# 10-DashLEDs.net
KiCad netlist of a schematic drawn in Altium Designer
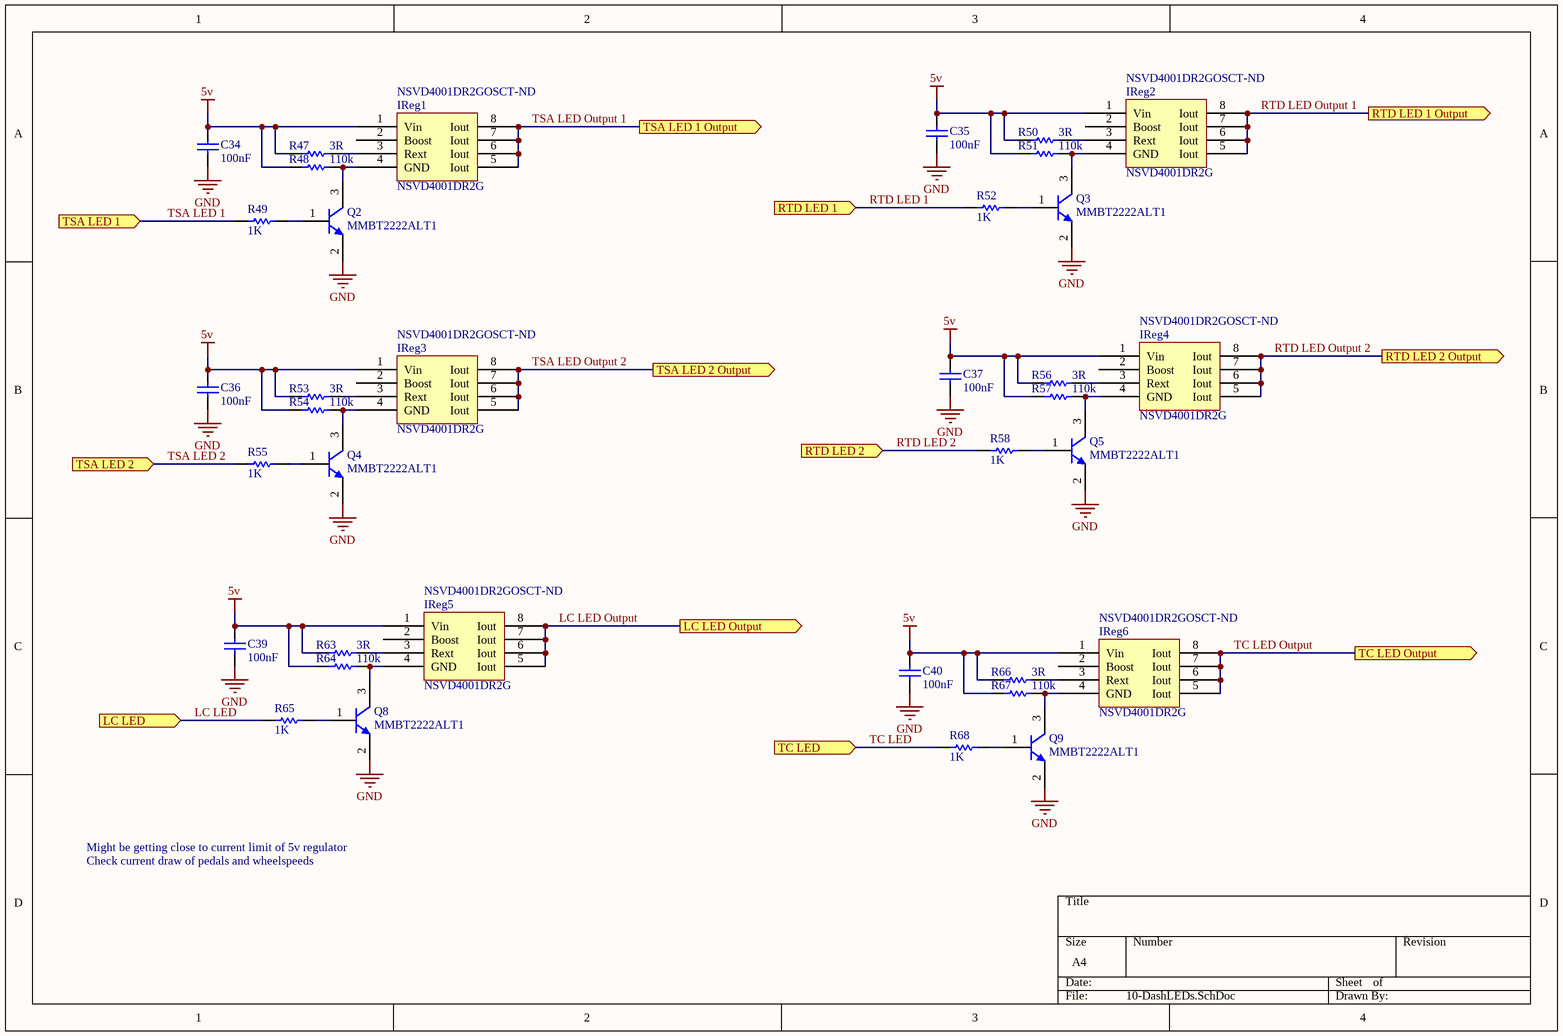
[diagram p0: 10-DashLEDs.SchDoc]

(export (version "E")
  (design (tool "Eeschema 10.0.6"))
  (components
    (comp (ref "C34")
      (value "100nF")
      (footprint "1608[0603]")
      (description "Capacitor")
      (fields
        (field (name "MANUFACTURER") "Yageo")
        (field (name "MANUFACTURER PART NUMBER") "CC0603KRX7R9BB104")
      )
      (libsource (lib "Miscellaneous Devices") (part "Cap"))
    )
    (comp (ref "C35")
      (value "100nF")
      (footprint "1608[0603]")
      (description "Capacitor")
      (fields
        (field (name "MANUFACTURER") "Yageo")
        (field (name "MANUFACTURER PART NUMBER") "CC0603KRX7R9BB104")
      )
      (libsource (lib "Miscellaneous Devices") (part "Cap"))
    )
    (comp (ref "C36")
      (value "100nF")
      (footprint "1608[0603]")
      (description "Capacitor")
      (fields
        (field (name "MANUFACTURER") "Yageo")
        (field (name "MANUFACTURER PART NUMBER") "CC0603KRX7R9BB104")
      )
      (libsource (lib "Miscellaneous Devices") (part "Cap"))
    )
    (comp (ref "C37")
      (value "100nF")
      (footprint "1608[0603]")
      (description "Capacitor")
      (fields
        (field (name "MANUFACTURER") "Yageo")
        (field (name "MANUFACTURER PART NUMBER") "CC0603KRX7R9BB104")
      )
      (libsource (lib "Miscellaneous Devices") (part "Cap"))
    )
    (comp (ref "C39")
      (value "100nF")
      (footprint "1608[0603]")
      (description "Capacitor")
      (fields
        (field (name "MANUFACTURER") "Yageo")
        (field (name "MANUFACTURER PART NUMBER") "CC0603KRX7R9BB104")
      )
      (libsource (lib "Miscellaneous Devices") (part "Cap"))
    )
    (comp (ref "C40")
      (value "100nF")
      (footprint "1608[0603]")
      (description "Capacitor")
      (fields
        (field (name "MANUFACTURER") "Yageo")
        (field (name "MANUFACTURER PART NUMBER") "CC0603KRX7R9BB104")
      )
      (libsource (lib "Miscellaneous Devices") (part "Cap"))
    )
    (comp (ref "IReg1")
      (value "NSVD4001DR2G")
      (footprint "SO8_M")
      (fields
        (field (name "MANUFACTURER") "ON Semiconductor")
        (field (name "MANUFACTURER PART NUMBER") "NUD4001DR2G")
        (field (name "SUPPLIER PART NUMBER 1") "NSVD4001DR2GOSCT-ND")
      )
      (libsource (lib "VCU Library") (part "LED Currnet Driver, 500mA, 30V max"))
    )
    (comp (ref "IReg2")
      (value "NSVD4001DR2G")
      (footprint "SO8_M")
      (fields
        (field (name "MANUFACTURER") "ON Semiconductor")
        (field (name "MANUFACTURER PART NUMBER") "NUD4001DR2G")
        (field (name "SUPPLIER PART NUMBER 1") "NSVD4001DR2GOSCT-ND")
      )
      (libsource (lib "VCU Library") (part "LED Currnet Driver, 500mA, 30V max"))
    )
    (comp (ref "IReg3")
      (value "NSVD4001DR2G")
      (footprint "SO8_M")
      (fields
        (field (name "MANUFACTURER") "ON Semiconductor")
        (field (name "MANUFACTURER PART NUMBER") "NUD4001DR2G")
        (field (name "SUPPLIER PART NUMBER 1") "NSVD4001DR2GOSCT-ND")
      )
      (libsource (lib "VCU Library") (part "LED Currnet Driver, 500mA, 30V max"))
    )
    (comp (ref "IReg4")
      (value "NSVD4001DR2G")
      (footprint "SO8_M")
      (fields
        (field (name "MANUFACTURER") "ON Semiconductor")
        (field (name "MANUFACTURER PART NUMBER") "NUD4001DR2G")
        (field (name "SUPPLIER PART NUMBER 1") "NSVD4001DR2GOSCT-ND")
      )
      (libsource (lib "VCU Library") (part "LED Currnet Driver, 500mA, 30V max"))
    )
    (comp (ref "IReg5")
      (value "NSVD4001DR2G")
      (footprint "SO8_M")
      (fields
        (field (name "MANUFACTURER") "ON Semiconductor")
        (field (name "MANUFACTURER PART NUMBER") "NUD4001DR2G")
        (field (name "SUPPLIER PART NUMBER 1") "NSVD4001DR2GOSCT-ND")
      )
      (libsource (lib "VCU Library") (part "LED Currnet Driver, 500mA, 30V max"))
    )
    (comp (ref "IReg6")
      (value "NSVD4001DR2G")
      (footprint "SO8_M")
      (fields
        (field (name "MANUFACTURER") "ON Semiconductor")
        (field (name "MANUFACTURER PART NUMBER") "NUD4001DR2G")
        (field (name "SUPPLIER PART NUMBER 1") "NSVD4001DR2GOSCT-ND")
      )
      (libsource (lib "VCU Library") (part "LED Currnet Driver, 500mA, 30V max"))
    )
    (comp (ref "Q2")
      (value "MMBT2222ALT1")
      (footprint "ONSC-SOT-23-3-318-08_V")
      (description "General Purpose Transistor, NPN Silicon, 3-Pin SOT-23, Tape and Reel")
      (fields (field (name "MANUFACTURER") "On Semiconductor"))
      (libsource (lib "Altium Content Vault") (part "ONSC-NPN-B1E2C3-3"))
    )
    (comp (ref "Q3")
      (value "MMBT2222ALT1")
      (footprint "ONSC-SOT-23-3-318-08_V")
      (description "General Purpose Transistor, NPN Silicon, 3-Pin SOT-23, Tape and Reel")
      (fields (field (name "MANUFACTURER") "On Semiconductor"))
      (libsource (lib "Altium Content Vault") (part "ONSC-NPN-B1E2C3-3"))
    )
    (comp (ref "Q4")
      (value "MMBT2222ALT1")
      (footprint "ONSC-SOT-23-3-318-08_V")
      (description "General Purpose Transistor, NPN Silicon, 3-Pin SOT-23, Tape and Reel")
      (fields (field (name "MANUFACTURER") "On Semiconductor"))
      (libsource (lib "Altium Content Vault") (part "ONSC-NPN-B1E2C3-3"))
    )
    (comp (ref "Q5")
      (value "MMBT2222ALT1")
      (footprint "ONSC-SOT-23-3-318-08_V")
      (description "General Purpose Transistor, NPN Silicon, 3-Pin SOT-23, Tape and Reel")
      (fields (field (name "MANUFACTURER") "On Semiconductor"))
      (libsource (lib "Altium Content Vault") (part "ONSC-NPN-B1E2C3-3"))
    )
    (comp (ref "Q8")
      (value "MMBT2222ALT1")
      (footprint "ONSC-SOT-23-3-318-08_V")
      (description "General Purpose Transistor, NPN Silicon, 3-Pin SOT-23, Tape and Reel")
      (fields (field (name "MANUFACTURER") "On Semiconductor"))
      (libsource (lib "Altium Content Vault") (part "ONSC-NPN-B1E2C3-3"))
    )
    (comp (ref "Q9")
      (value "MMBT2222ALT1")
      (footprint "ONSC-SOT-23-3-318-08_V")
      (description "General Purpose Transistor, NPN Silicon, 3-Pin SOT-23, Tape and Reel")
      (fields (field (name "MANUFACTURER") "On Semiconductor"))
      (libsource (lib "Altium Content Vault") (part "ONSC-NPN-B1E2C3-3"))
    )
    (comp (ref "R47")
      (value "3R")
      (footprint "1608[0603]")
      (description "Resistor")
      (fields
        (field (name "MANUFACTURER") "Yageo")
        (field (name "MANUFACTURER PART NUMBER") "RC0603FR-072RL")
      )
      (libsource (lib "Miscellaneous Devices") (part "Res1"))
    )
    (comp (ref "R48")
      (value "110k")
      (footprint "1608[0603]")
      (description "Resistor")
      (fields
        (field (name "MANUFACTURER") "Yageo")
        (field (name "MANUFACTURER PART NUMBER") "RC0603JR-07110KL")
      )
      (libsource (lib "Miscellaneous Devices") (part "Res1"))
    )
    (comp (ref "R49")
      (value "1K")
      (footprint "1608[0603]")
      (description "Resistor")
      (fields
        (field (name "MANUFACTURER") "Panasonic Electronic Components")
        (field (name "MANUFACTURER PART NUMBER") "ERJ-PA3F1001V")
      )
      (libsource (lib "Miscellaneous Devices") (part "Res1"))
    )
    (comp (ref "R50")
      (value "3R")
      (footprint "1608[0603]")
      (description "Resistor")
      (fields
        (field (name "MANUFACTURER") "Yageo")
        (field (name "MANUFACTURER PART NUMBER") "RC0603FR-072RL")
      )
      (libsource (lib "Miscellaneous Devices") (part "Res1"))
    )
    (comp (ref "R51")
      (value "110k")
      (footprint "1608[0603]")
      (description "Resistor")
      (fields
        (field (name "MANUFACTURER") "Yageo")
        (field (name "MANUFACTURER PART NUMBER") "RC0603JR-07110KL")
      )
      (libsource (lib "Miscellaneous Devices") (part "Res1"))
    )
    (comp (ref "R52")
      (value "1K")
      (footprint "1608[0603]")
      (description "Resistor")
      (fields
        (field (name "MANUFACTURER") "Panasonic Electronic Components")
        (field (name "MANUFACTURER PART NUMBER") "ERJ-PA3F1001V")
      )
      (libsource (lib "Miscellaneous Devices") (part "Res1"))
    )
    (comp (ref "R53")
      (value "3R")
      (footprint "1608[0603]")
      (description "Resistor")
      (fields
        (field (name "MANUFACTURER") "Yageo")
        (field (name "MANUFACTURER PART NUMBER") "RC0603FR-072RL")
      )
      (libsource (lib "Miscellaneous Devices") (part "Res1"))
    )
    (comp (ref "R54")
      (value "110k")
      (footprint "1608[0603]")
      (description "Resistor")
      (fields
        (field (name "MANUFACTURER") "Yageo")
        (field (name "MANUFACTURER PART NUMBER") "RC0603JR-07110KL")
      )
      (libsource (lib "Miscellaneous Devices") (part "Res1"))
    )
    (comp (ref "R55")
      (value "1K")
      (footprint "1608[0603]")
      (description "Resistor")
      (fields
        (field (name "MANUFACTURER") "Panasonic Electronic Components")
        (field (name "MANUFACTURER PART NUMBER") "ERJ-PA3F1001V")
      )
      (libsource (lib "Miscellaneous Devices") (part "Res1"))
    )
    (comp (ref "R56")
      (value "3R")
      (footprint "1608[0603]")
      (description "Resistor")
      (fields
        (field (name "MANUFACTURER") "Yageo")
        (field (name "MANUFACTURER PART NUMBER") "RC0603FR-072RL")
      )
      (libsource (lib "Miscellaneous Devices") (part "Res1"))
    )
    (comp (ref "R57")
      (value "110k")
      (footprint "1608[0603]")
      (description "Resistor")
      (fields
        (field (name "MANUFACTURER") "Yageo")
        (field (name "MANUFACTURER PART NUMBER") "RC0603JR-07110KL")
      )
      (libsource (lib "Miscellaneous Devices") (part "Res1"))
    )
    (comp (ref "R58")
      (value "1K")
      (footprint "1608[0603]")
      (description "Resistor")
      (fields
        (field (name "MANUFACTURER") "Panasonic Electronic Components")
        (field (name "MANUFACTURER PART NUMBER") "ERJ-PA3F1001V")
      )
      (libsource (lib "Miscellaneous Devices") (part "Res1"))
    )
    (comp (ref "R63")
      (value "3R")
      (footprint "1608[0603]")
      (description "Resistor")
      (fields
        (field (name "MANUFACTURER") "Yageo")
        (field (name "MANUFACTURER PART NUMBER") "RC0603FR-072RL")
      )
      (libsource (lib "Miscellaneous Devices") (part "Res1"))
    )
    (comp (ref "R64")
      (value "110k")
      (footprint "1608[0603]")
      (description "Resistor")
      (fields
        (field (name "MANUFACTURER") "Yageo")
        (field (name "MANUFACTURER PART NUMBER") "RC0603JR-07110KL")
      )
      (libsource (lib "Miscellaneous Devices") (part "Res1"))
    )
    (comp (ref "R65")
      (value "1K")
      (footprint "1608[0603]")
      (description "Resistor")
      (fields
        (field (name "MANUFACTURER") "Panasonic Electronic Components")
        (field (name "MANUFACTURER PART NUMBER") "ERJ-PA3F1001V")
      )
      (libsource (lib "Miscellaneous Devices") (part "Res1"))
    )
    (comp (ref "R66")
      (value "3R")
      (footprint "1608[0603]")
      (description "Resistor")
      (fields
        (field (name "MANUFACTURER") "Yageo")
        (field (name "MANUFACTURER PART NUMBER") "RC0603FR-072RL")
      )
      (libsource (lib "Miscellaneous Devices") (part "Res1"))
    )
    (comp (ref "R67")
      (value "110k")
      (footprint "1608[0603]")
      (description "Resistor")
      (fields
        (field (name "MANUFACTURER") "Yageo")
        (field (name "MANUFACTURER PART NUMBER") "RC0603JR-07110KL")
      )
      (libsource (lib "Miscellaneous Devices") (part "Res1"))
    )
    (comp (ref "R68")
      (value "1K")
      (footprint "1608[0603]")
      (description "Resistor")
      (fields
        (field (name "MANUFACTURER") "Panasonic Electronic Components")
        (field (name "MANUFACTURER PART NUMBER") "ERJ-PA3F1001V")
      )
      (libsource (lib "Miscellaneous Devices") (part "Res1"))
    )
  )
  (nets
    (net (code "1") (name "/LC LED") (class "Default")
      (node (ref "R65") (pin "2") (pinfunction "2_2") (pintype "passive"))
    )
    (net (code "2") (name "/LC LED Output") (class "Default")
      (node (ref "IReg5") (pin "5") (pinfunction "Iout_5") (pintype "passive"))
      (node (ref "IReg5") (pin "6") (pinfunction "Iout_6") (pintype "passive"))
      (node (ref "IReg5") (pin "7") (pinfunction "Iout_7") (pintype "passive"))
      (node (ref "IReg5") (pin "8") (pinfunction "Iout_8") (pintype "passive"))
    )
    (net (code "3") (name "/RTD LED 1") (class "Default")
      (node (ref "R52") (pin "2") (pinfunction "2_2") (pintype "passive"))
    )
    (net (code "4") (name "/RTD LED 2") (class "Default")
      (node (ref "R58") (pin "2") (pinfunction "2_2") (pintype "passive"))
    )
    (net (code "5") (name "/RTD LED Output 1") (class "Default")
      (node (ref "IReg2") (pin "5") (pinfunction "Iout_5") (pintype "passive"))
      (node (ref "IReg2") (pin "6") (pinfunction "Iout_6") (pintype "passive"))
      (node (ref "IReg2") (pin "7") (pinfunction "Iout_7") (pintype "passive"))
      (node (ref "IReg2") (pin "8") (pinfunction "Iout_8") (pintype "passive"))
    )
    (net (code "6") (name "/RTD LED Output 2") (class "Default")
      (node (ref "IReg4") (pin "5") (pinfunction "Iout_5") (pintype "passive"))
      (node (ref "IReg4") (pin "6") (pinfunction "Iout_6") (pintype "passive"))
      (node (ref "IReg4") (pin "7") (pinfunction "Iout_7") (pintype "passive"))
      (node (ref "IReg4") (pin "8") (pinfunction "Iout_8") (pintype "passive"))
    )
    (net (code "7") (name "/TC LED") (class "Default")
      (node (ref "R68") (pin "2") (pinfunction "2_2") (pintype "passive"))
    )
    (net (code "8") (name "/TC LED Output") (class "Default")
      (node (ref "IReg6") (pin "5") (pinfunction "Iout_5") (pintype "passive"))
      (node (ref "IReg6") (pin "6") (pinfunction "Iout_6") (pintype "passive"))
      (node (ref "IReg6") (pin "7") (pinfunction "Iout_7") (pintype "passive"))
      (node (ref "IReg6") (pin "8") (pinfunction "Iout_8") (pintype "passive"))
    )
    (net (code "9") (name "/TSA LED 1") (class "Default")
      (node (ref "R49") (pin "2") (pinfunction "2_2") (pintype "passive"))
    )
    (net (code "10") (name "/TSA LED 2") (class "Default")
      (node (ref "R55") (pin "2") (pinfunction "2_2") (pintype "passive"))
    )
    (net (code "11") (name "/TSA LED Output 1") (class "Default")
      (node (ref "IReg1") (pin "5") (pinfunction "Iout_5") (pintype "passive"))
      (node (ref "IReg1") (pin "6") (pinfunction "Iout_6") (pintype "passive"))
      (node (ref "IReg1") (pin "7") (pinfunction "Iout_7") (pintype "passive"))
      (node (ref "IReg1") (pin "8") (pinfunction "Iout_8") (pintype "passive"))
    )
    (net (code "12") (name "/TSA LED Output 2") (class "Default")
      (node (ref "IReg3") (pin "5") (pinfunction "Iout_5") (pintype "passive"))
      (node (ref "IReg3") (pin "6") (pinfunction "Iout_6") (pintype "passive"))
      (node (ref "IReg3") (pin "7") (pinfunction "Iout_7") (pintype "passive"))
      (node (ref "IReg3") (pin "8") (pinfunction "Iout_8") (pintype "passive"))
    )
    (net (code "13") (name "5v") (class "Default")
      (node (ref "C34") (pin "2") (pinfunction "2_2") (pintype "passive"))
      (node (ref "C35") (pin "2") (pinfunction "2_2") (pintype "passive"))
      (node (ref "C36") (pin "2") (pinfunction "2_2") (pintype "passive"))
      (node (ref "C37") (pin "2") (pinfunction "2_2") (pintype "passive"))
      (node (ref "C39") (pin "2") (pinfunction "2_2") (pintype "passive"))
      (node (ref "C40") (pin "2") (pinfunction "2_2") (pintype "passive"))
      (node (ref "IReg1") (pin "1") (pinfunction "Vin_1") (pintype "passive"))
      (node (ref "IReg2") (pin "1") (pinfunction "Vin_1") (pintype "passive"))
      (node (ref "IReg3") (pin "1") (pinfunction "Vin_1") (pintype "passive"))
      (node (ref "IReg4") (pin "1") (pinfunction "Vin_1") (pintype "passive"))
      (node (ref "IReg5") (pin "1") (pinfunction "Vin_1") (pintype "passive"))
      (node (ref "IReg6") (pin "1") (pinfunction "Vin_1") (pintype "passive"))
      (node (ref "R47") (pin "1") (pinfunction "1_1") (pintype "passive"))
      (node (ref "R48") (pin "1") (pinfunction "1_1") (pintype "passive"))
      (node (ref "R50") (pin "1") (pinfunction "1_1") (pintype "passive"))
      (node (ref "R51") (pin "1") (pinfunction "1_1") (pintype "passive"))
      (node (ref "R53") (pin "1") (pinfunction "1_1") (pintype "passive"))
      (node (ref "R54") (pin "1") (pinfunction "1_1") (pintype "passive"))
      (node (ref "R56") (pin "1") (pinfunction "1_1") (pintype "passive"))
      (node (ref "R57") (pin "1") (pinfunction "1_1") (pintype "passive"))
      (node (ref "R63") (pin "1") (pinfunction "1_1") (pintype "passive"))
      (node (ref "R64") (pin "1") (pinfunction "1_1") (pintype "passive"))
      (node (ref "R66") (pin "1") (pinfunction "1_1") (pintype "passive"))
      (node (ref "R67") (pin "1") (pinfunction "1_1") (pintype "passive"))
    )
    (net (code "14") (name "GND") (class "Default")
      (node (ref "C34") (pin "1") (pinfunction "1_1") (pintype "passive"))
      (node (ref "C35") (pin "1") (pinfunction "1_1") (pintype "passive"))
      (node (ref "C36") (pin "1") (pinfunction "1_1") (pintype "passive"))
      (node (ref "C37") (pin "1") (pinfunction "1_1") (pintype "passive"))
      (node (ref "C39") (pin "1") (pinfunction "1_1") (pintype "passive"))
      (node (ref "C40") (pin "1") (pinfunction "1_1") (pintype "passive"))
      (node (ref "Q2") (pin "2") (pinfunction "E_2") (pintype "passive"))
      (node (ref "Q3") (pin "2") (pinfunction "E_2") (pintype "passive"))
      (node (ref "Q4") (pin "2") (pinfunction "E_2") (pintype "passive"))
      (node (ref "Q5") (pin "2") (pinfunction "E_2") (pintype "passive"))
      (node (ref "Q8") (pin "2") (pinfunction "E_2") (pintype "passive"))
      (node (ref "Q9") (pin "2") (pinfunction "E_2") (pintype "passive"))
    )
    (net (code "15") (name "Net-(IReg1-GND)") (class "Default")
      (node (ref "IReg1") (pin "4") (pinfunction "GND_4") (pintype "passive"))
      (node (ref "Q2") (pin "3") (pinfunction "C_3") (pintype "passive"))
      (node (ref "R48") (pin "2") (pinfunction "2_2") (pintype "passive"))
    )
    (net (code "16") (name "Net-(IReg1-Rext)") (class "Default")
      (node (ref "IReg1") (pin "3") (pinfunction "Rext_3") (pintype "passive"))
      (node (ref "R47") (pin "2") (pinfunction "2_2") (pintype "passive"))
    )
    (net (code "17") (name "Net-(IReg2-GND)") (class "Default")
      (node (ref "IReg2") (pin "4") (pinfunction "GND_4") (pintype "passive"))
      (node (ref "Q3") (pin "3") (pinfunction "C_3") (pintype "passive"))
      (node (ref "R51") (pin "2") (pinfunction "2_2") (pintype "passive"))
    )
    (net (code "18") (name "Net-(IReg2-Rext)") (class "Default")
      (node (ref "IReg2") (pin "3") (pinfunction "Rext_3") (pintype "passive"))
      (node (ref "R50") (pin "2") (pinfunction "2_2") (pintype "passive"))
    )
    (net (code "19") (name "Net-(IReg3-GND)") (class "Default")
      (node (ref "IReg3") (pin "4") (pinfunction "GND_4") (pintype "passive"))
      (node (ref "Q4") (pin "3") (pinfunction "C_3") (pintype "passive"))
      (node (ref "R54") (pin "2") (pinfunction "2_2") (pintype "passive"))
    )
    (net (code "20") (name "Net-(IReg3-Rext)") (class "Default")
      (node (ref "IReg3") (pin "3") (pinfunction "Rext_3") (pintype "passive"))
      (node (ref "R53") (pin "2") (pinfunction "2_2") (pintype "passive"))
    )
    (net (code "21") (name "Net-(IReg4-GND)") (class "Default")
      (node (ref "IReg4") (pin "4") (pinfunction "GND_4") (pintype "passive"))
      (node (ref "Q5") (pin "3") (pinfunction "C_3") (pintype "passive"))
      (node (ref "R57") (pin "2") (pinfunction "2_2") (pintype "passive"))
    )
    (net (code "22") (name "Net-(IReg4-Rext)") (class "Default")
      (node (ref "IReg4") (pin "3") (pinfunction "Rext_3") (pintype "passive"))
      (node (ref "R56") (pin "2") (pinfunction "2_2") (pintype "passive"))
    )
    (net (code "23") (name "Net-(IReg5-GND)") (class "Default")
      (node (ref "IReg5") (pin "4") (pinfunction "GND_4") (pintype "passive"))
      (node (ref "Q8") (pin "3") (pinfunction "C_3") (pintype "passive"))
      (node (ref "R64") (pin "2") (pinfunction "2_2") (pintype "passive"))
    )
    (net (code "24") (name "Net-(IReg5-Rext)") (class "Default")
      (node (ref "IReg5") (pin "3") (pinfunction "Rext_3") (pintype "passive"))
      (node (ref "R63") (pin "2") (pinfunction "2_2") (pintype "passive"))
    )
    (net (code "25") (name "Net-(IReg6-GND)") (class "Default")
      (node (ref "IReg6") (pin "4") (pinfunction "GND_4") (pintype "passive"))
      (node (ref "Q9") (pin "3") (pinfunction "C_3") (pintype "passive"))
      (node (ref "R67") (pin "2") (pinfunction "2_2") (pintype "passive"))
    )
    (net (code "26") (name "Net-(IReg6-Rext)") (class "Default")
      (node (ref "IReg6") (pin "3") (pinfunction "Rext_3") (pintype "passive"))
      (node (ref "R66") (pin "2") (pinfunction "2_2") (pintype "passive"))
    )
    (net (code "27") (name "Net-(Q2-B)") (class "Default")
      (node (ref "Q2") (pin "1") (pinfunction "B_1") (pintype "passive"))
      (node (ref "R49") (pin "1") (pinfunction "1_1") (pintype "passive"))
    )
    (net (code "28") (name "Net-(Q3-B)") (class "Default")
      (node (ref "Q3") (pin "1") (pinfunction "B_1") (pintype "passive"))
      (node (ref "R52") (pin "1") (pinfunction "1_1") (pintype "passive"))
    )
    (net (code "29") (name "Net-(Q4-B)") (class "Default")
      (node (ref "Q4") (pin "1") (pinfunction "B_1") (pintype "passive"))
      (node (ref "R55") (pin "1") (pinfunction "1_1") (pintype "passive"))
    )
    (net (code "30") (name "Net-(Q5-B)") (class "Default")
      (node (ref "Q5") (pin "1") (pinfunction "B_1") (pintype "passive"))
      (node (ref "R58") (pin "1") (pinfunction "1_1") (pintype "passive"))
    )
    (net (code "31") (name "Net-(Q8-B)") (class "Default")
      (node (ref "Q8") (pin "1") (pinfunction "B_1") (pintype "passive"))
      (node (ref "R65") (pin "1") (pinfunction "1_1") (pintype "passive"))
    )
    (net (code "32") (name "Net-(Q9-B)") (class "Default")
      (node (ref "Q9") (pin "1") (pinfunction "B_1") (pintype "passive"))
      (node (ref "R68") (pin "1") (pinfunction "1_1") (pintype "passive"))
    )
    (net (code "33") (name "unconnected-(IReg1-Boost-Pad2)") (class "Default")
      (node (ref "IReg1") (pin "2") (pinfunction "Boost_2") (pintype "passive"))
    )
    (net (code "34") (name "unconnected-(IReg2-Boost-Pad2)") (class "Default")
      (node (ref "IReg2") (pin "2") (pinfunction "Boost_2") (pintype "passive"))
    )
    (net (code "35") (name "unconnected-(IReg3-Boost-Pad2)") (class "Default")
      (node (ref "IReg3") (pin "2") (pinfunction "Boost_2") (pintype "passive"))
    )
    (net (code "36") (name "unconnected-(IReg4-Boost-Pad2)") (class "Default")
      (node (ref "IReg4") (pin "2") (pinfunction "Boost_2") (pintype "passive"))
    )
    (net (code "37") (name "unconnected-(IReg5-Boost-Pad2)") (class "Default")
      (node (ref "IReg5") (pin "2") (pinfunction "Boost_2") (pintype "passive"))
    )
    (net (code "38") (name "unconnected-(IReg6-Boost-Pad2)") (class "Default")
      (node (ref "IReg6") (pin "2") (pinfunction "Boost_2") (pintype "passive"))
    )
  )
)
